# OpenPLCv0_2_0_1Wire.net
KiCad netlist of a schematic drawn in Altium Designer
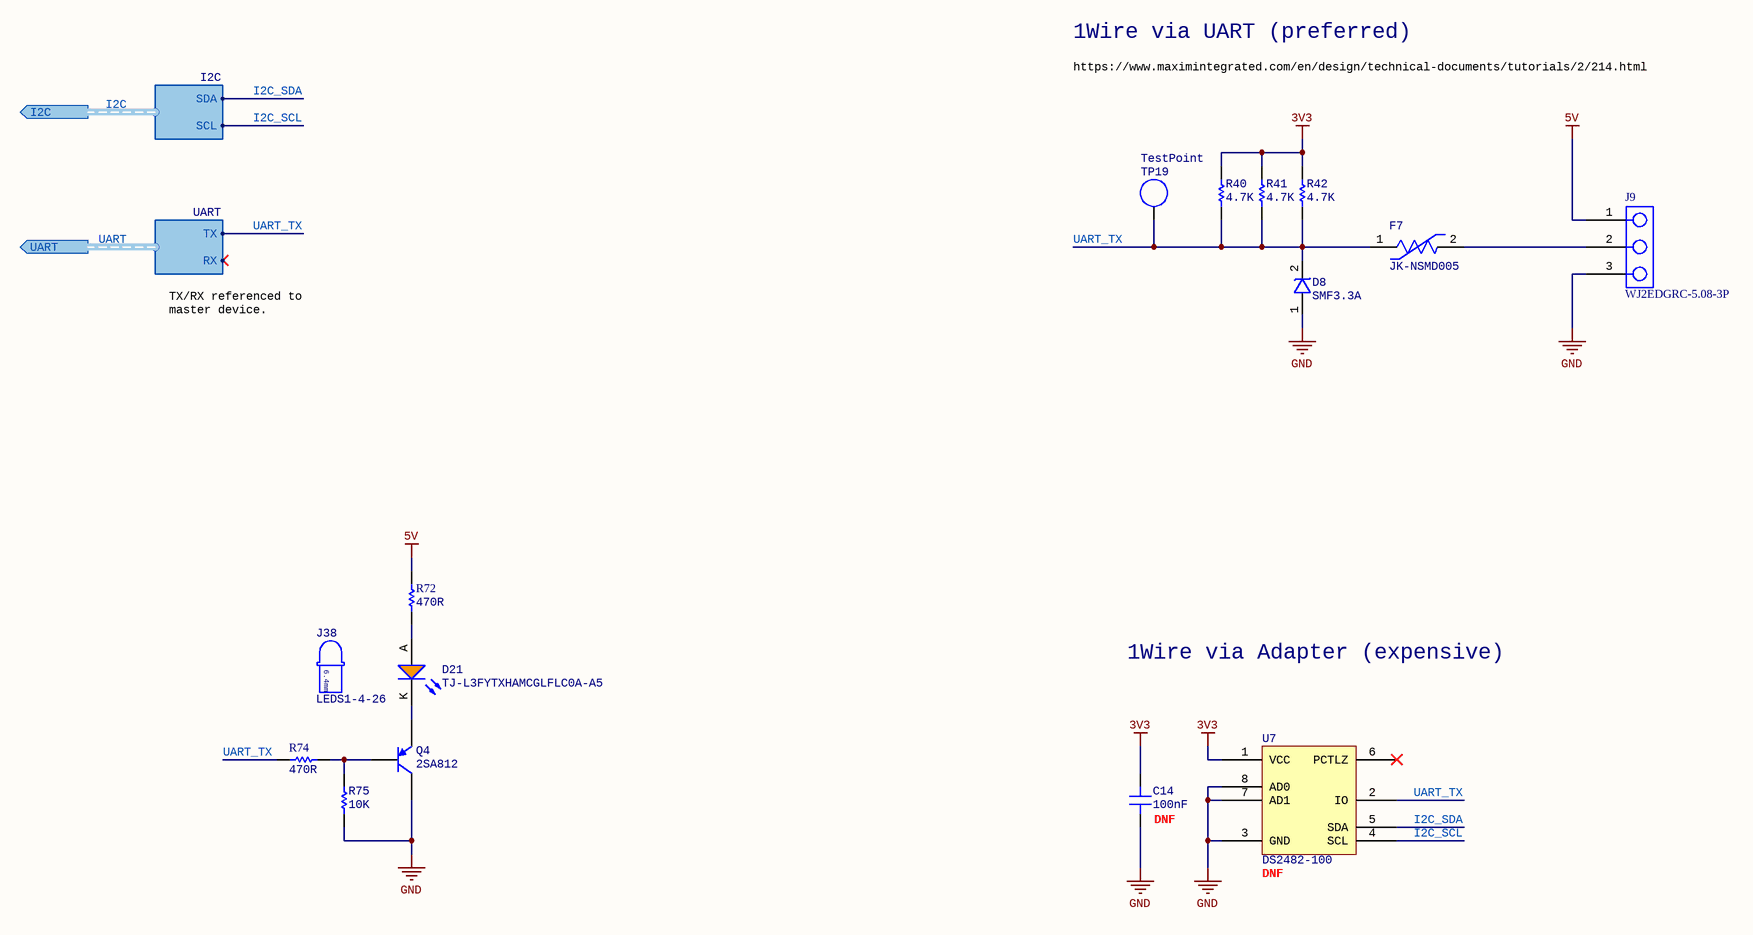
[diagram p0: OpenPLCv0.2.0_1Wire.SchDoc]

(export (version "E")
  (design (tool "Eeschema 10.0.6"))
  (components
    (comp (ref "C14")
      (value "CC0402KRX5R6BB104")
      (footprint "SMD_CAP_0402(1005)_N")
      (description "100nF ±10% 10V X5R 0402 Multilayer Ceramic Capacitors MLCC - SMD/SMT RoHS")
      (fields (field (name "TOLERANCE") "10%") (field (name "CAPACITANCE") "100nF"))
      (libsource (lib "BrauV2_Capacitor") (part "100nF 0402 10V 10%"))
    )
    (comp (ref "D8")
      (value "SMF3.3A")
      (footprint "SOD-123FL")
      (description "Unidirectional 3.3V 5.2V 8V 25A SOD-123 TVS RoHS")
      (libsource (lib "BrauV2_Diode") (part "SMF3.3A"))
    )
    (comp (ref "D21")
      (value "TJ-L3FYTXHAMCGLFLC0A-A5")
      (footprint "LED_3MM_SPACED_6.4MM_YELLOW")
      (description "600nm~610nm 1.8V~2.6V - - Through Hole Light Emitting Diodes (LED) ROHS 3mm")
      (libsource (lib "OpenPLCv0.2.0_Diode") (part "TJ-L3FYTXHAMCGLFLC0A-A5"))
    )
    (comp (ref "F7")
      (value "JK-NSMD005")
      (footprint "SMD_RES_1206(3216)_N")
      (description "60V 150mA 1.5s 1206 PTC Resettable Fuses RoHS")
      (libsource (lib "BrauV2_Resistor") (part "JK-NSMD005"))
    )
    (comp (ref "J9")
      (value "WJ2EDGRC-5.08-3P")
      (footprint "796638-3_BoardEdgeAlt")
      (description "Covered（4Sided） 3 1 0.200\"（5.08mm） 3 P=5.08mm Pluggable System Terminal Block RoHS")
      (libsource (lib "OpenPLCv0.2.0_Connector") (part "WJ2EDGRC-5.08-3P"))
    )
    (comp (ref "J38")
      (value "LEDS1-4-26")
      (footprint "3MM_LED_SPACER_6.4MM")
      (description "3mm LED spacer 6.4mm height")
      (libsource (lib "BrauV2_Misc") (part "LEDS1-4-26"))
    )
    (comp (ref "Q4")
      (value "2SA812")
      (footprint "SOT23-3")
      (description "SOT-23(SOT-23-3) Bipolar Transistors - BJT ROHS PNP")
      (libsource (lib "OpenPLCv0.2.0_Transistor") (part "2SA812"))
    )
    (comp (ref "R40")
      (value "RC0402FR-074K7L")
      (footprint "SMD_RES_0402(1005)_N")
      (description "4.7kΩ ±1% 1/16W ±100ppm/℃ 0402 Chip Resistor - Surface Mount RoHS")
      (fields (field (name "TOLERANCE") "1%") (field (name "RESISTANCE") "4.7K"))
      (libsource (lib "BrauV2_Resistor") (part "4K7 0402 1% 1/16W"))
    )
    (comp (ref "R41")
      (value "RC0402FR-074K7L")
      (footprint "SMD_RES_0402(1005)_N")
      (description "4.7kΩ ±1% 1/16W ±100ppm/℃ 0402 Chip Resistor - Surface Mount RoHS")
      (fields (field (name "TOLERANCE") "1%") (field (name "RESISTANCE") "4.7K"))
      (libsource (lib "BrauV2_Resistor") (part "4K7 0402 1% 1/16W"))
    )
    (comp (ref "R42")
      (value "RC0402FR-074K7L")
      (footprint "SMD_RES_0402(1005)_N")
      (description "4.7kΩ ±1% 1/16W ±100ppm/℃ 0402 Chip Resistor - Surface Mount RoHS")
      (fields (field (name "TOLERANCE") "1%") (field (name "RESISTANCE") "4.7K"))
      (libsource (lib "BrauV2_Resistor") (part "4K7 0402 1% 1/16W"))
    )
    (comp (ref "R72")
      (value "RC0402FR-07470RL")
      (footprint "SMD_RES_0402(1005)_N")
      (description "470Ω ±1% 1/16W ±100ppm/℃ 0402 Chip Resistor - Surface Mount RoHS")
      (fields (field (name "TOLERANCE") "1%") (field (name "RESISTANCE") "470R"))
      (libsource (lib "BrauV2_Resistor") (part "470R 0402 1% 1W"))
    )
    (comp (ref "R74")
      (value "RC0402FR-07470RL")
      (footprint "SMD_RES_0402(1005)_N")
      (description "470Ω ±1% 1/16W ±100ppm/℃ 0402 Chip Resistor - Surface Mount RoHS")
      (fields (field (name "TOLERANCE") "1%") (field (name "RESISTANCE") "470R"))
      (libsource (lib "BrauV2_Resistor") (part "470R 0402 1% 1W"))
    )
    (comp (ref "R75")
      (value "RC0402FR-0710KL")
      (footprint "SMD_RES_0402(1005)_N")
      (description "10kΩ ±1% 1/16W ±100ppm/℃ 0402 Chip Resistor - Surface Mount RoHS")
      (fields (field (name "TOLERANCE") "1%") (field (name "RESISTANCE") "10K"))
      (libsource (lib "BrauV2_Resistor") (part "10K 0402 1% 1/16W"))
    )
    (comp (ref "TP19")
      (value "TestPoint")
      (footprint "Pad")
      (libsource (lib "OpenPLCv0.2.0_Misc") (part "Test point"))
    )
    (comp (ref "U7")
      (value "DS2482-100")
      (footprint "SOIC-8-3.9mm")
      (description "Single-Channel 1-Wire Master")
      (libsource (lib "BrauV2_IC") (part "DS2482-100"))
    )
  )
  (nets
    (net (code "3") (name "/I2C_SCL") (class "Default")
      (node (ref "U7") (pin "4") (pinfunction "SCL_4") (pintype "passive"))
    )
    (net (code "4") (name "/I2C_SDA") (class "Default")
      (node (ref "U7") (pin "5") (pinfunction "SDA_5") (pintype "passive"))
    )
    (net (code "6") (name "/UART_TX") (class "Default")
      (node (ref "D8") (pin "2") (pinfunction "CATHODE_2") (pintype "passive"))
      (node (ref "F7") (pin "1") (pinfunction "1_1") (pintype "passive"))
      (node (ref "R40") (pin "1") (pinfunction "1_1") (pintype "passive"))
      (node (ref "R41") (pin "1") (pinfunction "1_1") (pintype "passive"))
      (node (ref "R42") (pin "1") (pinfunction "1_1") (pintype "passive"))
      (node (ref "R74") (pin "2") (pinfunction "2_2") (pintype "passive"))
      (node (ref "TP19") (pin "1") (pinfunction "1_1") (pintype "passive"))
      (node (ref "U7") (pin "2") (pinfunction "IO_2") (pintype "passive"))
    )
    (net (code "8") (name "3V3") (class "Default")
      (node (ref "C14") (pin "2") (pinfunction "2_2") (pintype "passive"))
      (node (ref "R40") (pin "2") (pinfunction "2_2") (pintype "passive"))
      (node (ref "R41") (pin "2") (pinfunction "2_2") (pintype "passive"))
      (node (ref "R42") (pin "2") (pinfunction "2_2") (pintype "passive"))
      (node (ref "U7") (pin "1") (pinfunction "VCC_1") (pintype "passive"))
    )
    (net (code "9") (name "5V") (class "Default")
      (node (ref "J9") (pin "1") (pinfunction "1_1") (pintype "passive"))
      (node (ref "R72") (pin "2") (pinfunction "2_2") (pintype "passive"))
    )
    (net (code "10") (name "GND") (class "Default")
      (node (ref "C14") (pin "1") (pinfunction "1_1") (pintype "passive"))
      (node (ref "D8") (pin "1") (pinfunction "ANODE_1") (pintype "passive"))
      (node (ref "J9") (pin "3") (pinfunction "3_3") (pintype "passive"))
      (node (ref "Q4") (pin "3") (pinfunction "E_3") (pintype "passive"))
      (node (ref "R75") (pin "1") (pinfunction "1_1") (pintype "passive"))
      (node (ref "U7") (pin "3") (pinfunction "GND_3") (pintype "passive"))
      (node (ref "U7") (pin "7") (pinfunction "AD1_7") (pintype "passive"))
      (node (ref "U7") (pin "8") (pinfunction "AD0_8") (pintype "passive"))
    )
    (net (code "11") (name "Net-(D21-PadA)") (class "Default")
      (node (ref "D21") (pin "A") (pinfunction "A_A") (pintype "passive"))
      (node (ref "R72") (pin "1") (pinfunction "1_1") (pintype "passive"))
    )
    (net (code "12") (name "Net-(F7-Pad2)") (class "Default")
      (node (ref "F7") (pin "2") (pinfunction "2_2") (pintype "passive"))
      (node (ref "J9") (pin "2") (pinfunction "2_2") (pintype "passive"))
    )
    (net (code "13") (name "Net-(Q4-B)") (class "Default")
      (node (ref "Q4") (pin "1") (pinfunction "B_1") (pintype "passive"))
      (node (ref "R74") (pin "1") (pinfunction "1_1") (pintype "passive"))
      (node (ref "R75") (pin "2") (pinfunction "2_2") (pintype "passive"))
    )
    (net (code "14") (name "Net-(Q4-C)") (class "Default")
      (node (ref "D21") (pin "K") (pinfunction "K_K") (pintype "passive"))
      (node (ref "Q4") (pin "2") (pinfunction "C_2") (pintype "passive"))
    )
    (net (code "15") (name "unconnected-(U7-PCTLZ-Pad6)") (class "Default")
      (node (ref "U7") (pin "6") (pinfunction "PCTLZ_6") (pintype "passive+no_connect"))
    )
  )
)
